# ESP32_BDB-1.net
KiCad netlist of a schematic drawn in Altium Designer
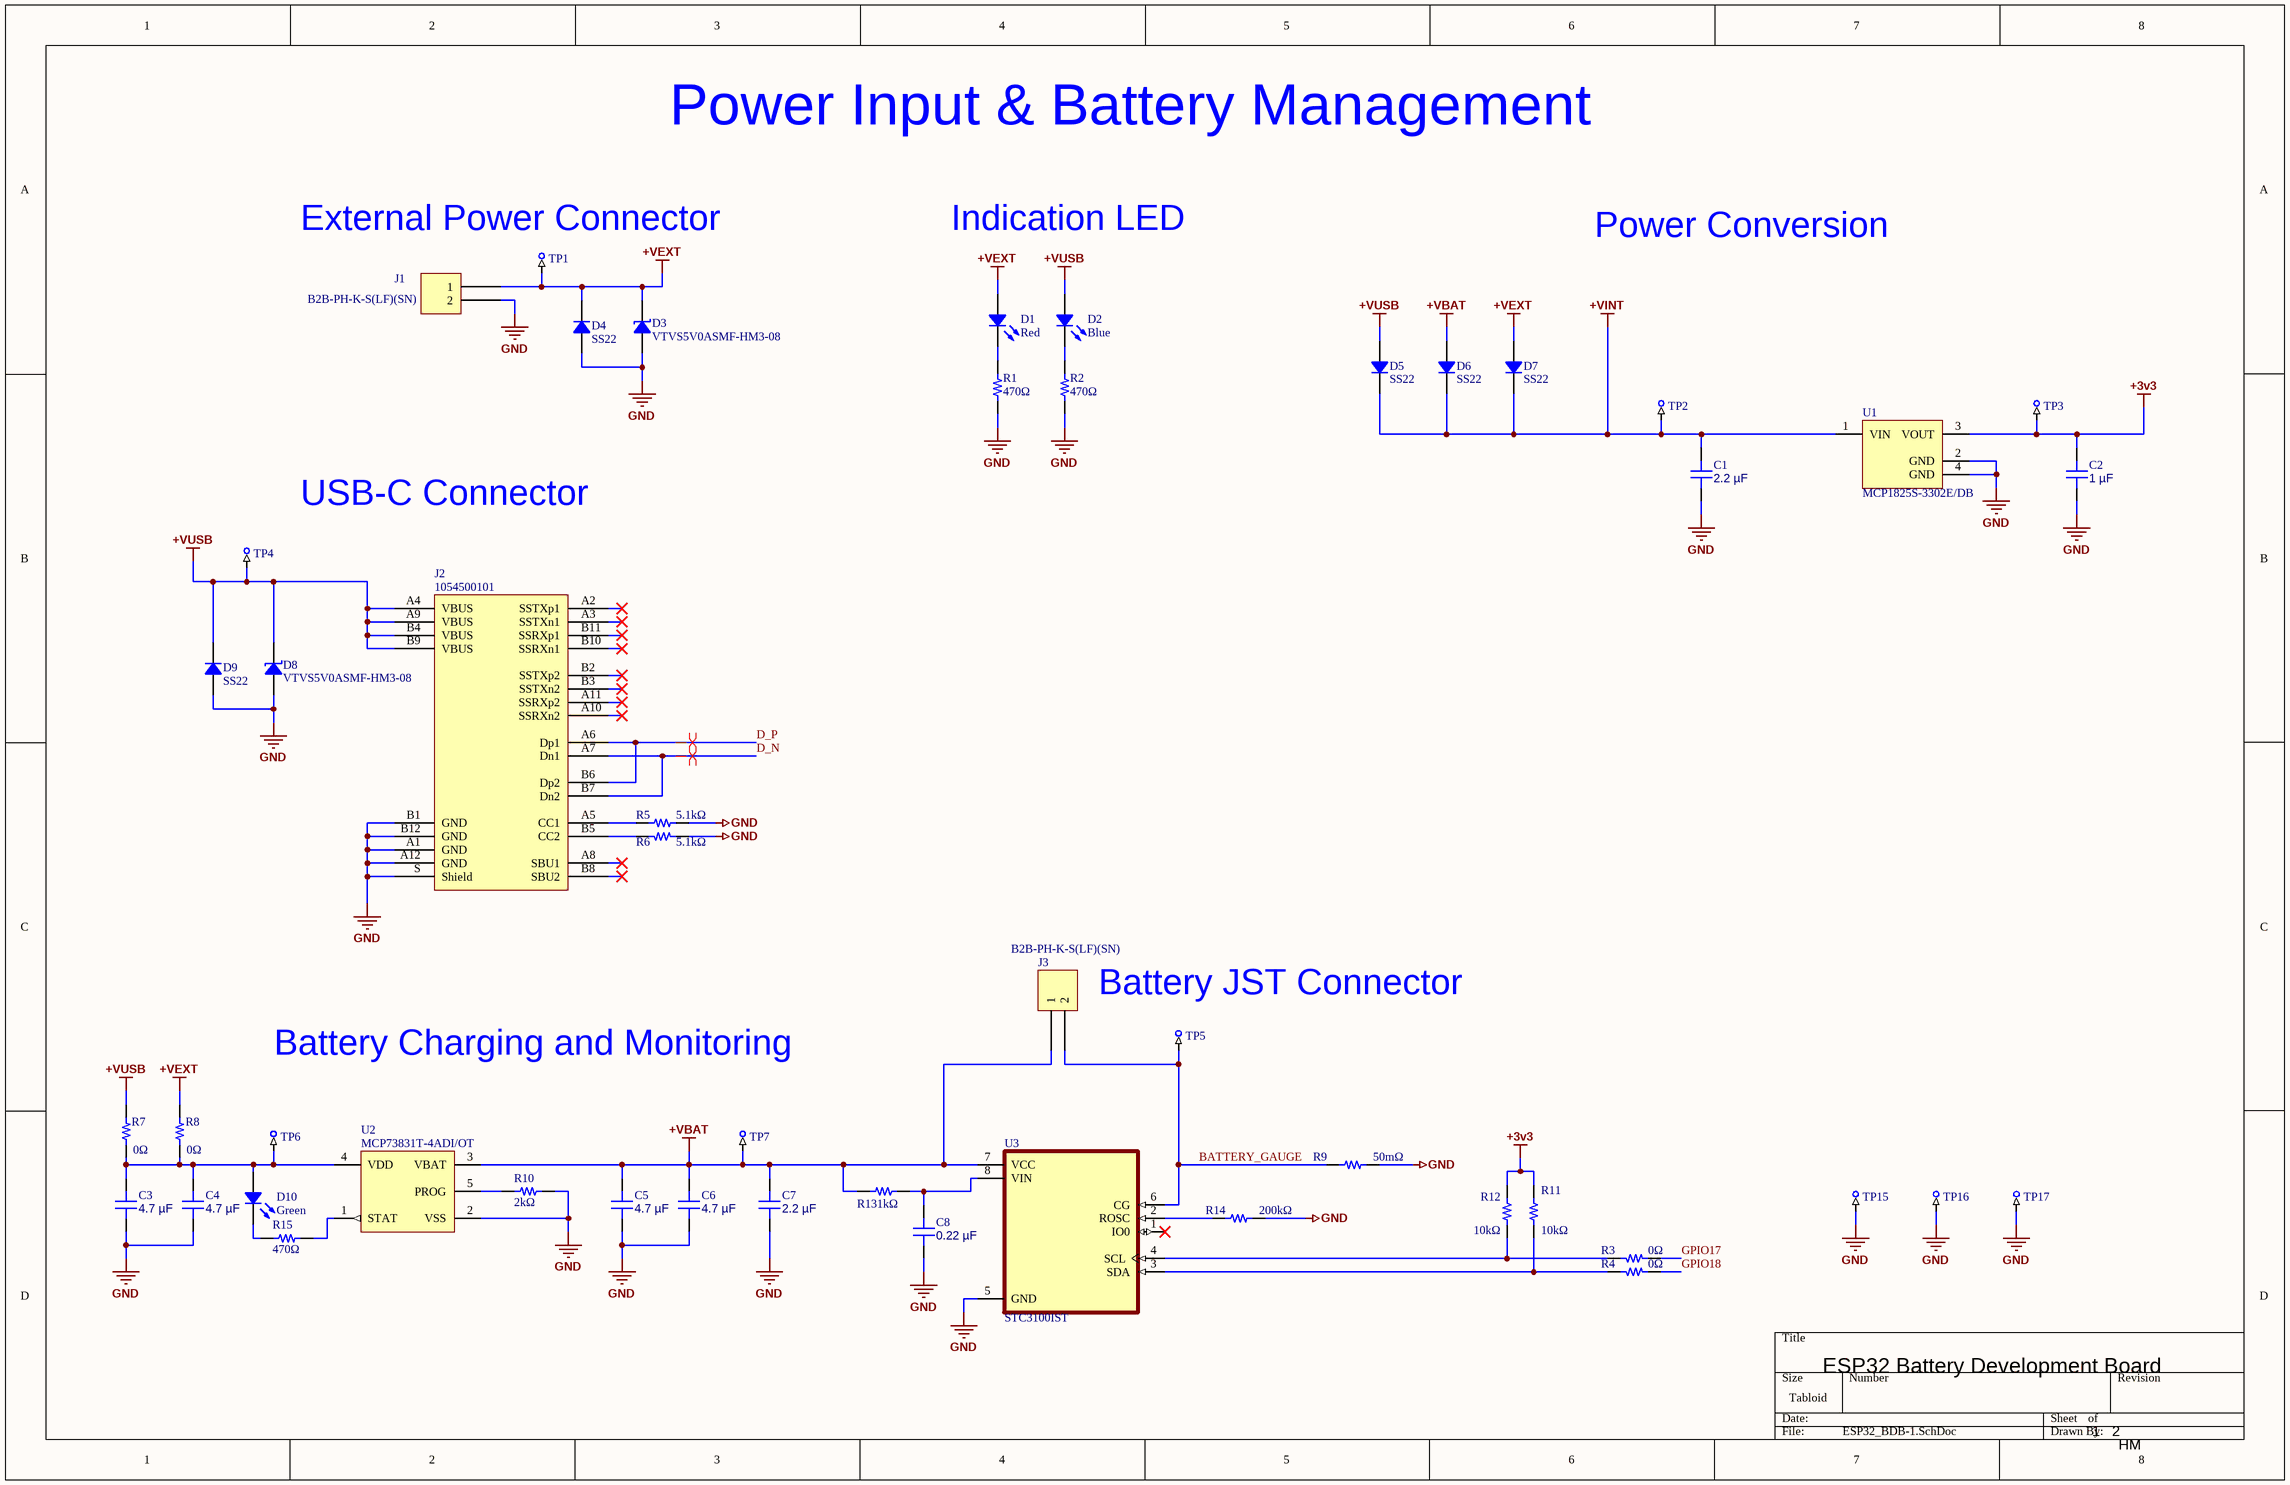
[diagram p0: ESP32_BDB-1.SchDoc]

(export (version "E")
  (design (tool "Eeschema 10.0.6"))
  (components
    (comp (ref "C1")
      (value "2.2 µF")
      (footprint "CAP 0805_2012")
      (description "CAP CER 2.2UF 25V X7R 0805")
      (fields
        (field (name "PART NUMBER") "0805B225K250CT")
        (field (name "CAPACITANCE") "2.2 µF")
        (field (name "MANUFACTURER") "Walsin Technology Corporation")
      )
      (libsource (lib "Celestial Altium Library - altium_library") (part "Capacitor"))
    )
    (comp (ref "C2")
      (value "1 µF")
      (footprint "CAP 0805_2012")
      (description "CAP CER 1UF 35V X7R 0805")
      (fields
        (field (name "PART NUMBER") "0805DC105KAT2A")
        (field (name "CAPACITANCE") "1 µF")
        (field (name "MANUFACTURER") "KYOCERA AVX")
      )
      (libsource (lib "Celestial Altium Library - altium_library") (part "Capacitor"))
    )
    (comp (ref "C3")
      (value "4.7 µF")
      (footprint "CAP 0805_2012")
      (description "CAP CER 4.7UF 25V X7R 0805")
      (fields
        (field (name "PART NUMBER") "CL21B475KAFNNNE")
        (field (name "CAPACITANCE") "4.7 µF")
        (field (name "MANUFACTURER") "Samsung Electro-Mechanics")
      )
      (libsource (lib "Celestial Altium Library - altium_library") (part "Capacitor"))
    )
    (comp (ref "C4")
      (value "4.7 µF")
      (footprint "CAP 0805_2012")
      (description "CAP CER 4.7UF 25V X7R 0805")
      (fields
        (field (name "PART NUMBER") "CL21B475KAFNNNE")
        (field (name "CAPACITANCE") "4.7 µF")
        (field (name "MANUFACTURER") "Samsung Electro-Mechanics")
      )
      (libsource (lib "Celestial Altium Library - altium_library") (part "Capacitor"))
    )
    (comp (ref "C5")
      (value "4.7 µF")
      (footprint "CAP 0805_2012")
      (description "CAP CER 4.7UF 25V X7R 0805")
      (fields
        (field (name "PART NUMBER") "CL21B475KAFNNNE")
        (field (name "CAPACITANCE") "4.7 µF")
        (field (name "MANUFACTURER") "Samsung Electro-Mechanics")
      )
      (libsource (lib "Celestial Altium Library - altium_library") (part "Capacitor"))
    )
    (comp (ref "C6")
      (value "4.7 µF")
      (footprint "CAP 0805_2012")
      (description "CAP CER 4.7UF 25V X7R 0805")
      (fields
        (field (name "PART NUMBER") "CL21B475KAFNNNE")
        (field (name "CAPACITANCE") "4.7 µF")
        (field (name "MANUFACTURER") "Samsung Electro-Mechanics")
      )
      (libsource (lib "Celestial Altium Library - altium_library") (part "Capacitor"))
    )
    (comp (ref "C7")
      (value "2.2 µF")
      (footprint "CAP 0603_1608")
      (description "CAP CER 2.2UF 16V Y5V 0603")
      (fields
        (field (name "PART NUMBER") "CC0603ZRY5V7BB225")
        (field (name "CAPACITANCE") "2.2 µF")
        (field (name "MANUFACTURER") "Yageo")
      )
      (libsource (lib "Celestial Altium Library - altium_library") (part "Capacitor"))
    )
    (comp (ref "C8")
      (value "0.22 µF")
      (footprint "CAP 0603_1608")
      (description "CAP CER 0603 220NF 16V X7R 5%")
      (fields
        (field (name "PART NUMBER") "C0603C224J4REC7867")
        (field (name "CAPACITANCE") "0.22 µF")
        (field (name "MANUFACTURER") "KEMET")
      )
      (libsource (lib "Celestial Altium Library - altium_library") (part "Capacitor"))
    )
    (comp (ref "D1")
      (value "Red")
      (footprint "LED 0805_2012 RED")
      (description "LED RED 0805 SMD")
      (fields (field (name "PART NUMBER") "5990110007F") (field (name "MANUFACTURER") "Dialight"))
      (libsource (lib "Celestial Altium Library - altium_library") (part "LED"))
    )
    (comp (ref "D2")
      (value "Blue")
      (footprint "LED 0805_2012 BLUE")
      (description "LED BLUE CLEAR 0805 SMD")
      (fields (field (name "PART NUMBER") "IN-S85AT5B") (field (name "MANUFACTURER") "Inolux"))
      (libsource (lib "Celestial Altium Library - altium_library") (part "LED"))
    )
    (comp (ref "D3")
      (value "VTVS5V0ASMF-HM3-08")
      (footprint "SMF DO-219AB")
      (description "TVS DIODE 5V 8.9V DO219AB")
      (fields (field (name "MANUFACTURER") "Vishay Semiconductor Diodes Division"))
      (libsource (lib "Celestial Altium Library - altium_library") (part "DIODE TVS UNI"))
    )
    (comp (ref "D4")
      (value "SS22")
      (footprint "DO214AA SMB")
      (description "DIODE SCHOTTKY 20V 2A DO214AA")
      (fields (field (name "MANUFACTURER") "ON Semiconductor"))
      (libsource (lib "Celestial Altium Library - altium_library") (part "Diode"))
    )
    (comp (ref "D5")
      (value "SS22")
      (footprint "DO214AA SMB")
      (description "DIODE SCHOTTKY 20V 2A DO214AA")
      (fields (field (name "MANUFACTURER") "ON Semiconductor"))
      (libsource (lib "Celestial Altium Library - altium_library") (part "Diode"))
    )
    (comp (ref "D6")
      (value "SS22")
      (footprint "DO214AA SMB")
      (description "DIODE SCHOTTKY 20V 2A DO214AA")
      (fields (field (name "MANUFACTURER") "ON Semiconductor"))
      (libsource (lib "Celestial Altium Library - altium_library") (part "Diode"))
    )
    (comp (ref "D7")
      (value "SS22")
      (footprint "DO214AA SMB")
      (description "DIODE SCHOTTKY 20V 2A DO214AA")
      (fields (field (name "MANUFACTURER") "ON Semiconductor"))
      (libsource (lib "Celestial Altium Library - altium_library") (part "Diode"))
    )
    (comp (ref "D8")
      (value "VTVS5V0ASMF-HM3-08")
      (footprint "SMF DO-219AB")
      (description "TVS DIODE 5V 8.9V DO219AB")
      (fields (field (name "MANUFACTURER") "Vishay Semiconductor Diodes Division"))
      (libsource (lib "Celestial Altium Library - altium_library") (part "DIODE TVS UNI"))
    )
    (comp (ref "D9")
      (value "SS22")
      (footprint "DO214AA SMB")
      (description "DIODE SCHOTTKY 20V 2A DO214AA")
      (fields (field (name "MANUFACTURER") "ON Semiconductor"))
      (libsource (lib "Celestial Altium Library - altium_library") (part "Diode"))
    )
    (comp (ref "D10")
      (value "Green")
      (footprint "LED 0805_2012 GREEN")
      (description "LED GREEN 0805 SMD")
      (fields (field (name "PART NUMBER") "5975316507F") (field (name "MANUFACTURER") "Dialight"))
      (libsource (lib "Celestial Altium Library - altium_library") (part "LED"))
    )
    (comp (ref "J1")
      (value "B2B-PH-K-S(LF)(SN)")
      (footprint "JST B2B-PH-K")
      (description "CONN HEADER VERT 2POS 2MM")
      (fields (field (name "MANUFACTURER") "JST Sales America Inc."))
      (libsource (lib "") (part "2 Pin_1"))
    )
    (comp (ref "J2")
      (value "1054500101")
      (footprint "Molex 1054500101")
      (description "CONN RCP USB3.1 TYPEC 24P SMD RA")
      (fields (field (name "MANUFACTURER") "Molex"))
      (libsource (lib "Celestial Altium Library - altium_library") (part "USB 3.0 Type C"))
    )
    (comp (ref "J3")
      (value "B2B-PH-K-S(LF)(SN)")
      (footprint "JST B2B-PH-K")
      (description "CONN HEADER VERT 2POS 2MM")
      (fields (field (name "MANUFACTURER") "JST Sales America Inc."))
      (libsource (lib "Celestial Altium Library - altium_library") (part "2 Pin"))
    )
    (comp (ref "R1")
      (value "470Ω")
      (footprint "RES 0603_1608")
      (description "RES 470 OHM 1% 1/5W 0603")
      (fields (field (name "PART NUMBER") "AC0603FR-7W470RL") (field (name "MANUFACTURER") "Yageo"))
      (libsource (lib "Celestial Altium Library - altium_library") (part "Resistor"))
    )
    (comp (ref "R2")
      (value "470Ω")
      (footprint "RES 0603_1608")
      (description "RES 470 OHM 1% 1/5W 0603")
      (fields (field (name "PART NUMBER") "AC0603FR-7W470RL") (field (name "MANUFACTURER") "Yageo"))
      (libsource (lib "Celestial Altium Library - altium_library") (part "Resistor"))
    )
    (comp (ref "R3")
      (value "0Ω")
      (footprint "RES 0805_2012")
      (description "RES 0 OHM JUMPER 0805")
      (fields
        (field (name "PART NUMBER") "TLRZ2ATTD")
        (field (name "MANUFACTURER") "KOA Speer Electronics, Inc.")
      )
      (libsource (lib "Celestial Altium Library - altium_library") (part "Resistor"))
    )
    (comp (ref "R4")
      (value "0Ω")
      (footprint "RES 0805_2012")
      (description "RES 0 OHM JUMPER 0805")
      (fields
        (field (name "PART NUMBER") "TLRZ2ATTD")
        (field (name "MANUFACTURER") "KOA Speer Electronics, Inc.")
      )
      (libsource (lib "Celestial Altium Library - altium_library") (part "Resistor"))
    )
    (comp (ref "R5")
      (value "5.1kΩ")
      (footprint "RES 0603_1608")
      (description "RES SMD 5.1K OHM 1% 1/10W 0603")
      (fields (field (name "PART NUMBER") "AC0603FR-075K1L") (field (name "MANUFACTURER") "Yageo"))
      (libsource (lib "Celestial Altium Library - altium_library") (part "Resistor"))
    )
    (comp (ref "R6")
      (value "5.1kΩ")
      (footprint "RES 0603_1608")
      (description "RES SMD 5.1K OHM 1% 1/10W 0603")
      (fields (field (name "PART NUMBER") "AC0603FR-075K1L") (field (name "MANUFACTURER") "Yageo"))
      (libsource (lib "Celestial Altium Library - altium_library") (part "Resistor"))
    )
    (comp (ref "R7")
      (value "0Ω")
      (footprint "RES 0805_2012")
      (description "RES 0 OHM JUMPER 0805")
      (fields
        (field (name "PART NUMBER") "TLRZ2ATTD")
        (field (name "MANUFACTURER") "KOA Speer Electronics, Inc.")
      )
      (libsource (lib "Celestial Altium Library - altium_library") (part "Resistor"))
    )
    (comp (ref "R8")
      (value "0Ω")
      (footprint "RES 0805_2012")
      (description "RES 0 OHM JUMPER 0805")
      (fields
        (field (name "PART NUMBER") "TLRZ2ATTD")
        (field (name "MANUFACTURER") "KOA Speer Electronics, Inc.")
      )
      (libsource (lib "Celestial Altium Library - altium_library") (part "Resistor"))
    )
    (comp (ref "R9")
      (value "50mΩ")
      (footprint "RES 0805_2012")
      (description "RES 0.05 OHM 1% 1/2W 0805")
      (fields
        (field (name "PART NUMBER") "RL-1220-4-R050-FNH")
        (field (name "MANUFACTURER") "Delta Electronics/Cyntec")
      )
      (libsource (lib "Celestial Altium Library - altium_library") (part "Resistor"))
    )
    (comp (ref "R10")
      (value "2kΩ")
      (footprint "RES 0603_1608")
      (description "RES 2K OHM 1% 1/5W 0603")
      (fields (field (name "PART NUMBER") "AC0603FR-7W2KL") (field (name "MANUFACTURER") "Yageo"))
      (libsource (lib "Celestial Altium Library - altium_library") (part "Resistor"))
    )
    (comp (ref "R11")
      (value "10kΩ")
      (footprint "RES 0603_1608")
      (description "RES SMD 10K OHM 1% 1/10W 0603")
      (fields (field (name "PART NUMBER") "AA0603FR-0710KL") (field (name "MANUFACTURER") "Yageo"))
      (libsource (lib "Celestial Altium Library - altium_library") (part "Resistor"))
    )
    (comp (ref "R12")
      (value "10kΩ")
      (footprint "RES 0603_1608")
      (description "RES SMD 10K OHM 1% 1/10W 0603")
      (fields (field (name "PART NUMBER") "AA0603FR-0710KL") (field (name "MANUFACTURER") "Yageo"))
      (libsource (lib "Celestial Altium Library - altium_library") (part "Resistor"))
    )
    (comp (ref "R13")
      (value "1kΩ")
      (footprint "RES 0603_1608")
      (description "RES SMD 1K OHM 1% 1/10W 0603")
      (fields (field (name "PART NUMBER") "AA0603FR-071KL") (field (name "MANUFACTURER") "Yageo"))
      (libsource (lib "Celestial Altium Library - altium_library") (part "Resistor"))
    )
    (comp (ref "R14")
      (value "200kΩ")
      (footprint "RES 0603_1608")
      (description "RES SMD 200K OHM 0.1% 1/10W 0603")
      (fields (field (name "PART NUMBER") "AT0603BRD07200KL") (field (name "MANUFACTURER") "Yageo"))
      (libsource (lib "Celestial Altium Library - altium_library") (part "Resistor"))
    )
    (comp (ref "R15")
      (value "470Ω")
      (footprint "RES 0603_1608")
      (description "RES 470 OHM 1% 1/5W 0603")
      (fields (field (name "PART NUMBER") "AC0603FR-7W470RL") (field (name "MANUFACTURER") "Yageo"))
      (libsource (lib "Celestial Altium Library - altium_library") (part "Resistor"))
    )
    (comp (ref "TP1")
      (value "5016")
      (footprint "KEYSTONE-5016_V")
      (description "Test Point, 1-Pin SMT, RoHS, Tape and Reel")
      (fields (field (name "MANUFACTURER") "Keystone"))
      (libsource (lib "Altium Content Vault") (part "KEYSTONE-5016"))
    )
    (comp (ref "TP2")
      (value "5016")
      (footprint "KEYSTONE-5016_V")
      (description "Test Point, 1-Pin SMT, RoHS, Tape and Reel")
      (fields (field (name "MANUFACTURER") "Keystone"))
      (libsource (lib "Altium Content Vault") (part "KEYSTONE-5016"))
    )
    (comp (ref "TP3")
      (value "5016")
      (footprint "KEYSTONE-5016_V")
      (description "Test Point, 1-Pin SMT, RoHS, Tape and Reel")
      (fields (field (name "MANUFACTURER") "Keystone"))
      (libsource (lib "Altium Content Vault") (part "KEYSTONE-5016"))
    )
    (comp (ref "TP4")
      (value "5016")
      (footprint "KEYSTONE-5016_V")
      (description "Test Point, 1-Pin SMT, RoHS, Tape and Reel")
      (fields (field (name "MANUFACTURER") "Keystone"))
      (libsource (lib "Altium Content Vault") (part "KEYSTONE-5016"))
    )
    (comp (ref "TP5")
      (value "5016")
      (footprint "KEYSTONE-5016_V")
      (description "Test Point, 1-Pin SMT, RoHS, Tape and Reel")
      (fields (field (name "MANUFACTURER") "Keystone"))
      (libsource (lib "Altium Content Vault") (part "KEYSTONE-5016"))
    )
    (comp (ref "TP6")
      (value "5016")
      (footprint "KEYSTONE-5016_V")
      (description "Test Point, 1-Pin SMT, RoHS, Tape and Reel")
      (fields (field (name "MANUFACTURER") "Keystone"))
      (libsource (lib "Altium Content Vault") (part "KEYSTONE-5016"))
    )
    (comp (ref "TP7")
      (value "5016")
      (footprint "KEYSTONE-5016_V")
      (description "Test Point, 1-Pin SMT, RoHS, Tape and Reel")
      (fields (field (name "MANUFACTURER") "Keystone"))
      (libsource (lib "Altium Content Vault") (part "KEYSTONE-5016"))
    )
    (comp (ref "TP15")
      (value "5016")
      (footprint "KEYSTONE-5016_V")
      (description "Test Point, 1-Pin SMT, RoHS, Tape and Reel")
      (fields (field (name "MANUFACTURER") "Keystone"))
      (libsource (lib "Altium Content Vault") (part "KEYSTONE-5016"))
    )
    (comp (ref "TP16")
      (value "5016")
      (footprint "KEYSTONE-5016_V")
      (description "Test Point, 1-Pin SMT, RoHS, Tape and Reel")
      (fields (field (name "MANUFACTURER") "Keystone"))
      (libsource (lib "Altium Content Vault") (part "KEYSTONE-5016"))
    )
    (comp (ref "TP17")
      (value "5016")
      (footprint "KEYSTONE-5016_V")
      (description "Test Point, 1-Pin SMT, RoHS, Tape and Reel")
      (fields (field (name "MANUFACTURER") "Keystone"))
      (libsource (lib "Altium Content Vault") (part "KEYSTONE-5016"))
    )
    (comp (ref "U1")
      (value "MCP1825S-3302E/DB")
      (footprint "SOT-223-DB3_N")
      (description "500 mA, Low Voltage, Low Quiescent Current LDO Regulator, 3-Pin SOT-223, Extended Temperature")
      (libsource (lib "Altium Content Vault") (part "PM-LINEREG-MCP1825-IL4"))
    )
    (comp (ref "U2")
      (value "MCP73831T-4ADI/OT")
      (footprint "SOT-23-OT5_N")
      (libsource (lib "Altium Content Vault") (part "PM-BM-MCP73831-SOT5"))
    )
    (comp (ref "U3")
      (value "STC3100IST")
      (footprint "SOIC65P490X110-8N")
      (description "Battery Battery Monitor IC Lithium Ion 8-MiniSO")
      (fields (field (name "MF") "STMicroelectronics"))
      (libsource (lib "STC3100IST") (part "STC3100IST"))
    )
  )
  (nets
    (net (code "1") (name "+3v3") (class "Default")
      (node (ref "C2") (pin "2") (pinfunction "2_2") (pintype "passive"))
      (node (ref "R11") (pin "2") (pinfunction "2_2") (pintype "passive"))
      (node (ref "R12") (pin "2") (pinfunction "2_2") (pintype "passive"))
      (node (ref "TP3") (pin "1") (pinfunction "1_1") (pintype "input"))
      (node (ref "U1") (pin "3") (pinfunction "VOUT_3") (pintype "power_in"))
    )
    (net (code "2") (name "+VBAT") (class "Default")
      (node (ref "C5") (pin "2") (pinfunction "2_2") (pintype "passive"))
      (node (ref "C6") (pin "2") (pinfunction "2_2") (pintype "passive"))
      (node (ref "C7") (pin "2") (pinfunction "2_2") (pintype "passive"))
      (node (ref "D6") (pin "1") (pinfunction "1_1") (pintype "passive"))
      (node (ref "J3") (pin "1") (pinfunction "1_1") (pintype "passive"))
      (node (ref "R13") (pin "1") (pinfunction "1_1") (pintype "passive"))
      (node (ref "TP7") (pin "1") (pinfunction "1_1") (pintype "input"))
      (node (ref "U2") (pin "3") (pinfunction "VBAT_3") (pintype "power_in"))
      (node (ref "U3") (pin "7") (pinfunction "VCC_7") (pintype "power_in"))
    )
    (net (code "3") (name "+VEXT") (class "Default")
      (node (ref "D1") (pin "1") (pinfunction "1_1") (pintype "passive"))
      (node (ref "D3") (pin "2") (pinfunction "2_2") (pintype "passive"))
      (node (ref "D4") (pin "2") (pinfunction "2_2") (pintype "passive"))
      (node (ref "D7") (pin "1") (pinfunction "1_1") (pintype "passive"))
      (node (ref "J1") (pin "1") (pinfunction "1_1") (pintype "passive"))
      (node (ref "R8") (pin "2") (pinfunction "2_2") (pintype "passive"))
      (node (ref "TP1") (pin "1") (pinfunction "1_1") (pintype "input"))
    )
    (net (code "4") (name "+VINT") (class "Default")
      (node (ref "C1") (pin "2") (pinfunction "2_2") (pintype "passive"))
      (node (ref "D5") (pin "2") (pinfunction "2_2") (pintype "passive"))
      (node (ref "D6") (pin "2") (pinfunction "2_2") (pintype "passive"))
      (node (ref "D7") (pin "2") (pinfunction "2_2") (pintype "passive"))
      (node (ref "TP2") (pin "1") (pinfunction "1_1") (pintype "input"))
      (node (ref "U1") (pin "1") (pinfunction "VIN_1") (pintype "power_in"))
    )
    (net (code "5") (name "+VUSB") (class "Default")
      (node (ref "D2") (pin "1") (pinfunction "1_1") (pintype "passive"))
      (node (ref "D5") (pin "1") (pinfunction "1_1") (pintype "passive"))
      (node (ref "D8") (pin "2") (pinfunction "2_2") (pintype "passive"))
      (node (ref "D9") (pin "2") (pinfunction "2_2") (pintype "passive"))
      (node (ref "J2") (pin "A4") (pinfunction "VBUS_A4") (pintype "passive"))
      (node (ref "J2") (pin "A9") (pinfunction "VBUS_A9") (pintype "passive"))
      (node (ref "J2") (pin "B4") (pinfunction "VBUS_B4") (pintype "passive"))
      (node (ref "J2") (pin "B9") (pinfunction "VBUS_B9") (pintype "passive"))
      (node (ref "R7") (pin "2") (pinfunction "2_2") (pintype "passive"))
      (node (ref "TP4") (pin "1") (pinfunction "1_1") (pintype "input"))
    )
    (net (code "6") (name "/BATTERY_GAUGE") (class "Default")
      (node (ref "J3") (pin "2") (pinfunction "2_2") (pintype "passive"))
      (node (ref "R9") (pin "1") (pinfunction "1_1") (pintype "passive"))
      (node (ref "TP5") (pin "1") (pinfunction "1_1") (pintype "input"))
      (node (ref "U3") (pin "6") (pinfunction "CG_6") (pintype "input"))
    )
    (net (code "7") (name "/D_N") (class "Default")
      (node (ref "J2") (pin "A7") (pinfunction "Dn1_A7") (pintype "passive"))
      (node (ref "J2") (pin "B7") (pinfunction "Dn2_B7") (pintype "passive"))
    )
    (net (code "8") (name "/D_P") (class "Default")
      (node (ref "J2") (pin "A6") (pinfunction "Dp1_A6") (pintype "passive"))
      (node (ref "J2") (pin "B6") (pinfunction "Dp2_B6") (pintype "passive"))
    )
    (net (code "9") (name "/GPIO17") (class "Default")
      (node (ref "R3") (pin "1") (pinfunction "1_1") (pintype "passive"))
    )
    (net (code "10") (name "/GPIO18") (class "Default")
      (node (ref "R4") (pin "1") (pinfunction "1_1") (pintype "passive"))
    )
    (net (code "11") (name "GND") (class "Default")
      (node (ref "C1") (pin "1") (pinfunction "1_1") (pintype "passive"))
      (node (ref "C2") (pin "1") (pinfunction "1_1") (pintype "passive"))
      (node (ref "C3") (pin "1") (pinfunction "1_1") (pintype "passive"))
      (node (ref "C4") (pin "1") (pinfunction "1_1") (pintype "passive"))
      (node (ref "C5") (pin "1") (pinfunction "1_1") (pintype "passive"))
      (node (ref "C6") (pin "1") (pinfunction "1_1") (pintype "passive"))
      (node (ref "C7") (pin "1") (pinfunction "1_1") (pintype "passive"))
      (node (ref "C8") (pin "1") (pinfunction "1_1") (pintype "passive"))
      (node (ref "D3") (pin "1") (pinfunction "1_1") (pintype "passive"))
      (node (ref "D4") (pin "1") (pinfunction "1_1") (pintype "passive"))
      (node (ref "D8") (pin "1") (pinfunction "1_1") (pintype "passive"))
      (node (ref "D9") (pin "1") (pinfunction "1_1") (pintype "passive"))
      (node (ref "J1") (pin "2") (pinfunction "2_2") (pintype "passive"))
      (node (ref "J2") (pin "A1") (pinfunction "GND_A1") (pintype "passive"))
      (node (ref "J2") (pin "A12") (pinfunction "GND_A12") (pintype "passive"))
      (node (ref "J2") (pin "B1") (pinfunction "GND_B1") (pintype "passive"))
      (node (ref "J2") (pin "B12") (pinfunction "GND_B12") (pintype "passive"))
      (node (ref "J2") (pin "S") (pinfunction "Shield_S") (pintype "passive"))
      (node (ref "R1") (pin "2") (pinfunction "2_2") (pintype "passive"))
      (node (ref "R10") (pin "1") (pinfunction "1_1") (pintype "passive"))
      (node (ref "R14") (pin "2") (pinfunction "2_2") (pintype "passive"))
      (node (ref "R2") (pin "2") (pinfunction "2_2") (pintype "passive"))
      (node (ref "R5") (pin "2") (pinfunction "2_2") (pintype "passive"))
      (node (ref "R6") (pin "2") (pinfunction "2_2") (pintype "passive"))
      (node (ref "R9") (pin "2") (pinfunction "2_2") (pintype "passive"))
      (node (ref "TP15") (pin "1") (pinfunction "1_1") (pintype "input"))
      (node (ref "TP16") (pin "1") (pinfunction "1_1") (pintype "input"))
      (node (ref "TP17") (pin "1") (pinfunction "1_1") (pintype "input"))
      (node (ref "U1") (pin "2") (pinfunction "GND_2") (pintype "power_in"))
      (node (ref "U1") (pin "4") (pinfunction "GND_4") (pintype "power_in"))
      (node (ref "U2") (pin "2") (pinfunction "VSS_2") (pintype "power_in"))
      (node (ref "U3") (pin "5") (pinfunction "GND_5") (pintype "power_in"))
    )
    (net (code "12") (name "Net-(D1-Pad2)") (class "Default")
      (node (ref "D1") (pin "2") (pinfunction "2_2") (pintype "passive"))
      (node (ref "R1") (pin "1") (pinfunction "1_1") (pintype "passive"))
    )
    (net (code "13") (name "Net-(D2-Pad2)") (class "Default")
      (node (ref "D2") (pin "2") (pinfunction "2_2") (pintype "passive"))
      (node (ref "R2") (pin "1") (pinfunction "1_1") (pintype "passive"))
    )
    (net (code "14") (name "Net-(D10-Pad2)") (class "Default")
      (node (ref "D10") (pin "2") (pinfunction "2_2") (pintype "passive"))
      (node (ref "R15") (pin "2") (pinfunction "2_2") (pintype "passive"))
    )
    (net (code "15") (name "Net-(J2-CC1)") (class "Default")
      (node (ref "J2") (pin "A5") (pinfunction "CC1_A5") (pintype "passive"))
      (node (ref "R5") (pin "1") (pinfunction "1_1") (pintype "passive"))
    )
    (net (code "16") (name "Net-(J2-CC2)") (class "Default")
      (node (ref "J2") (pin "B5") (pinfunction "CC2_B5") (pintype "passive"))
      (node (ref "R6") (pin "1") (pinfunction "1_1") (pintype "passive"))
    )
    (net (code "17") (name "Net-(U2-PROG)") (class "Default")
      (node (ref "R10") (pin "2") (pinfunction "2_2") (pintype "passive"))
      (node (ref "U2") (pin "5") (pinfunction "PROG_5") (pintype "passive"))
    )
    (net (code "18") (name "Net-(U2-STAT)") (class "Default")
      (node (ref "R15") (pin "1") (pinfunction "1_1") (pintype "passive"))
      (node (ref "U2") (pin "1") (pinfunction "STAT_1") (pintype "output"))
    )
    (net (code "19") (name "Net-(U2-VDD)") (class "Default")
      (node (ref "C3") (pin "2") (pinfunction "2_2") (pintype "passive"))
      (node (ref "C4") (pin "2") (pinfunction "2_2") (pintype "passive"))
      (node (ref "D10") (pin "1") (pinfunction "1_1") (pintype "passive"))
      (node (ref "R7") (pin "1") (pinfunction "1_1") (pintype "passive"))
      (node (ref "R8") (pin "1") (pinfunction "1_1") (pintype "passive"))
      (node (ref "TP6") (pin "1") (pinfunction "1_1") (pintype "input"))
      (node (ref "U2") (pin "4") (pinfunction "VDD_4") (pintype "power_in"))
    )
    (net (code "20") (name "Net-(U3-ROSC)") (class "Default")
      (node (ref "R14") (pin "1") (pinfunction "1_1") (pintype "passive"))
      (node (ref "U3") (pin "2") (pinfunction "ROSC_2") (pintype "input"))
    )
    (net (code "21") (name "Net-(U3-SCL)") (class "Default")
      (node (ref "R12") (pin "1") (pinfunction "1_1") (pintype "passive"))
      (node (ref "R3") (pin "2") (pinfunction "2_2") (pintype "passive"))
      (node (ref "U3") (pin "4") (pinfunction "SCL_4") (pintype "input"))
    )
    (net (code "22") (name "Net-(U3-SDA)") (class "Default")
      (node (ref "R11") (pin "1") (pinfunction "1_1") (pintype "passive"))
      (node (ref "R4") (pin "2") (pinfunction "2_2") (pintype "passive"))
      (node (ref "U3") (pin "3") (pinfunction "SDA_3") (pintype "input"))
    )
    (net (code "23") (name "Net-(U3-VIN)") (class "Default")
      (node (ref "C8") (pin "2") (pinfunction "2_2") (pintype "passive"))
      (node (ref "R13") (pin "2") (pinfunction "2_2") (pintype "passive"))
      (node (ref "U3") (pin "8") (pinfunction "VIN_8") (pintype "power_in"))
    )
    (net (code "24") (name "unconnected-(J2-SBU1-PadA8)") (class "Default")
      (node (ref "J2") (pin "A8") (pinfunction "SBU1_A8") (pintype "passive+no_connect"))
    )
    (net (code "25") (name "unconnected-(J2-SBU2-PadB8)") (class "Default")
      (node (ref "J2") (pin "B8") (pinfunction "SBU2_B8") (pintype "passive+no_connect"))
    )
    (net (code "26") (name "unconnected-(J2-SSRXn1-PadB10)") (class "Default")
      (node (ref "J2") (pin "B10") (pinfunction "SSRXn1_B10") (pintype "passive+no_connect"))
    )
    (net (code "27") (name "unconnected-(J2-SSRXn2-PadA10)") (class "Default")
      (node (ref "J2") (pin "A10") (pinfunction "SSRXn2_A10") (pintype "passive+no_connect"))
    )
    (net (code "28") (name "unconnected-(J2-SSRXp1-PadB11)") (class "Default")
      (node (ref "J2") (pin "B11") (pinfunction "SSRXp1_B11") (pintype "passive+no_connect"))
    )
    (net (code "29") (name "unconnected-(J2-SSRXp2-PadA11)") (class "Default")
      (node (ref "J2") (pin "A11") (pinfunction "SSRXp2_A11") (pintype "passive+no_connect"))
    )
    (net (code "30") (name "unconnected-(J2-SSTXn1-PadA3)") (class "Default")
      (node (ref "J2") (pin "A3") (pinfunction "SSTXn1_A3") (pintype "passive+no_connect"))
    )
    (net (code "31") (name "unconnected-(J2-SSTXn2-PadB3)") (class "Default")
      (node (ref "J2") (pin "B3") (pinfunction "SSTXn2_B3") (pintype "passive+no_connect"))
    )
    (net (code "32") (name "unconnected-(J2-SSTXp1-PadA2)") (class "Default")
      (node (ref "J2") (pin "A2") (pinfunction "SSTXp1_A2") (pintype "passive+no_connect"))
    )
    (net (code "33") (name "unconnected-(J2-SSTXp2-PadB2)") (class "Default")
      (node (ref "J2") (pin "B2") (pinfunction "SSTXp2_B2") (pintype "passive+no_connect"))
    )
    (net (code "34") (name "unconnected-(U3-IO0-Pad1)") (class "Default")
      (node (ref "U3") (pin "1") (pinfunction "IO0_1") (pintype "bidirectional+no_connect"))
    )
  )
)
